# 8x8.net
KiCad netlist of a schematic drawn in EAGLE
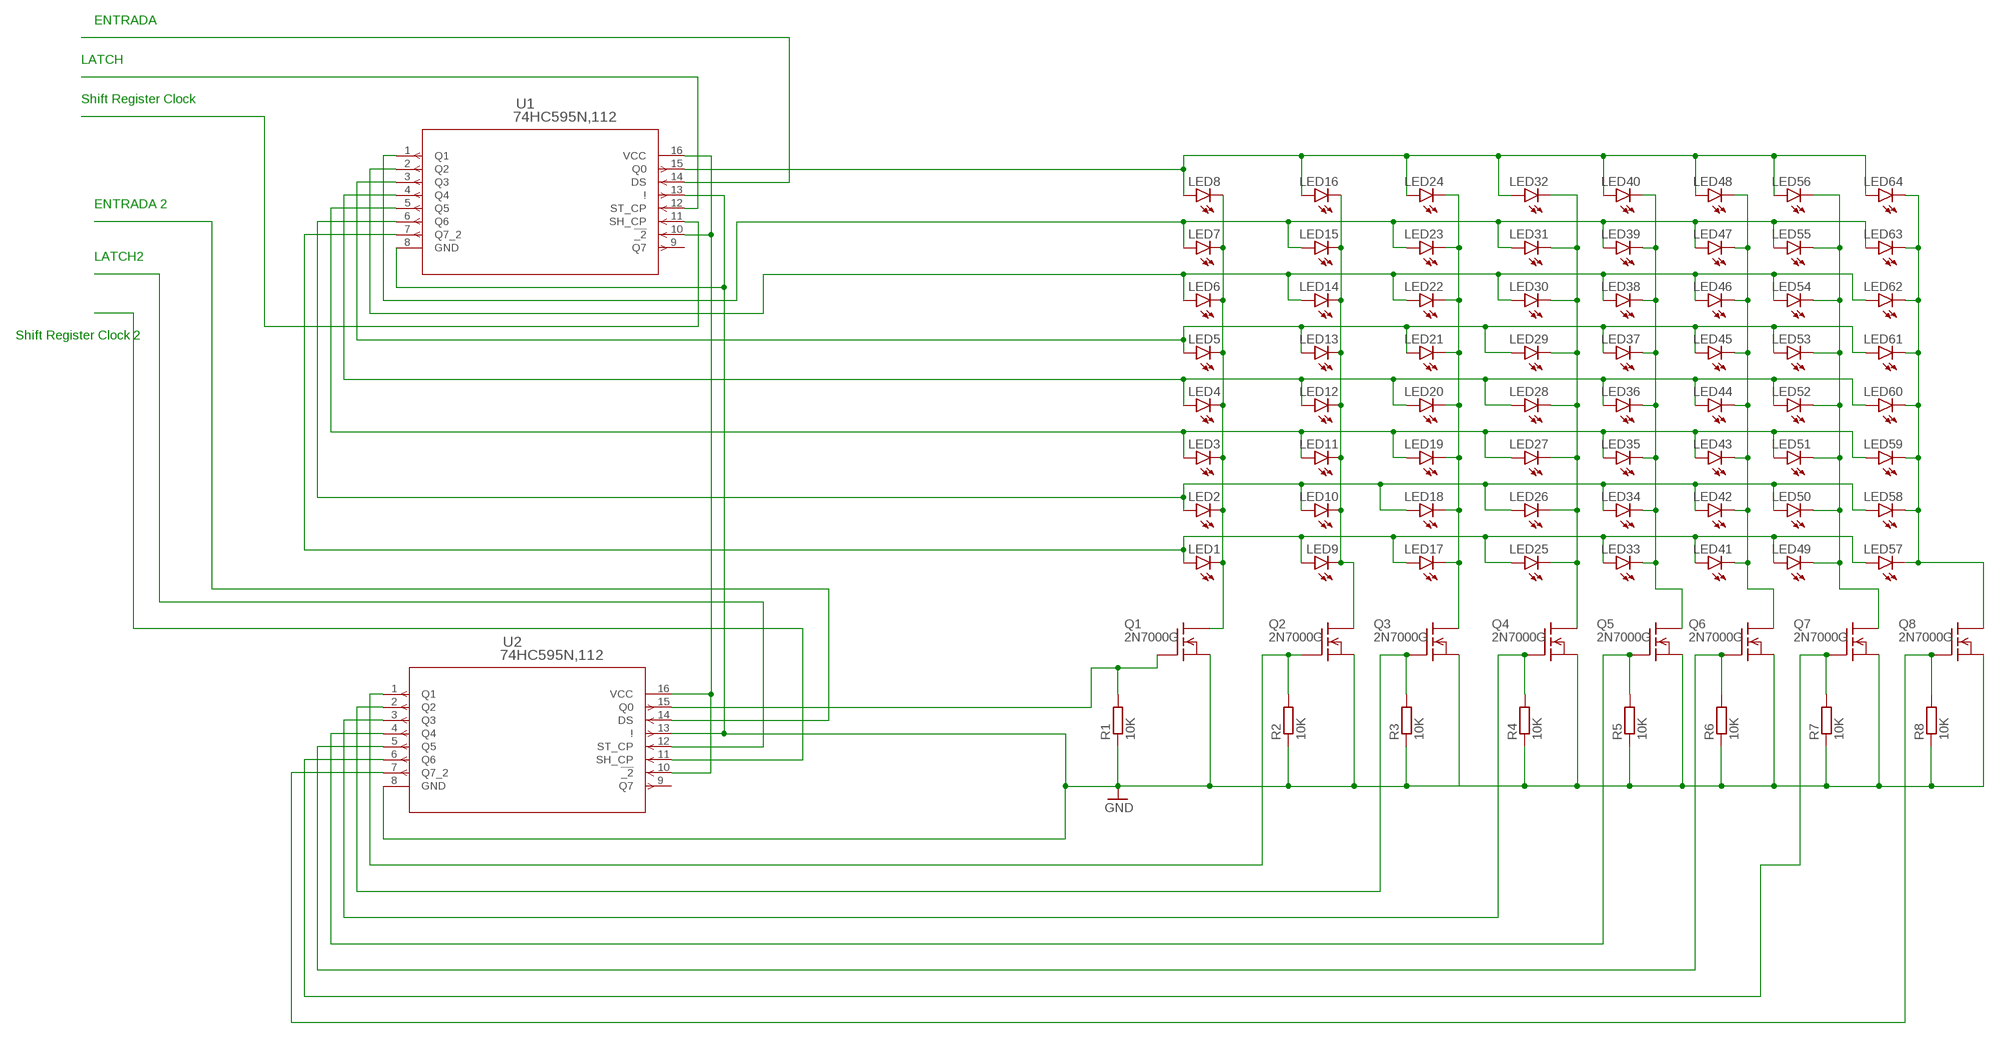
[diagram p0: schematic, sheet 1]

(export (version "E")
  (design (tool "Eeschema 10.0.6"))
  (components
    (comp (ref "LED1")
      (value "LED3MM")
      (footprint "eagle-import:LED3MM")
      (libsource (lib "eagle-import") (part "LED3MM"))
    )
    (comp (ref "LED2")
      (value "LED3MM")
      (footprint "eagle-import:LED3MM")
      (libsource (lib "eagle-import") (part "LED3MM"))
    )
    (comp (ref "LED3")
      (value "LED3MM")
      (footprint "eagle-import:LED3MM")
      (libsource (lib "eagle-import") (part "LED3MM"))
    )
    (comp (ref "LED4")
      (value "LED3MM")
      (footprint "eagle-import:LED3MM")
      (libsource (lib "eagle-import") (part "LED3MM"))
    )
    (comp (ref "LED5")
      (value "LED3MM")
      (footprint "eagle-import:LED3MM")
      (libsource (lib "eagle-import") (part "LED3MM"))
    )
    (comp (ref "LED6")
      (value "LED3MM")
      (footprint "eagle-import:LED3MM")
      (libsource (lib "eagle-import") (part "LED3MM"))
    )
    (comp (ref "LED7")
      (value "LED3MM")
      (footprint "eagle-import:LED3MM")
      (libsource (lib "eagle-import") (part "LED3MM"))
    )
    (comp (ref "LED8")
      (value "LED3MM")
      (footprint "eagle-import:LED3MM")
      (libsource (lib "eagle-import") (part "LED3MM"))
    )
    (comp (ref "LED9")
      (value "LED3MM")
      (footprint "eagle-import:LED3MM")
      (libsource (lib "eagle-import") (part "LED3MM"))
    )
    (comp (ref "LED10")
      (value "LED3MM")
      (footprint "eagle-import:LED3MM")
      (libsource (lib "eagle-import") (part "LED3MM"))
    )
    (comp (ref "LED11")
      (value "LED3MM")
      (footprint "eagle-import:LED3MM")
      (libsource (lib "eagle-import") (part "LED3MM"))
    )
    (comp (ref "LED12")
      (value "LED3MM")
      (footprint "eagle-import:LED3MM")
      (libsource (lib "eagle-import") (part "LED3MM"))
    )
    (comp (ref "LED13")
      (value "LED3MM")
      (footprint "eagle-import:LED3MM")
      (libsource (lib "eagle-import") (part "LED3MM"))
    )
    (comp (ref "LED14")
      (value "LED3MM")
      (footprint "eagle-import:LED3MM")
      (libsource (lib "eagle-import") (part "LED3MM"))
    )
    (comp (ref "LED15")
      (value "LED3MM")
      (footprint "eagle-import:LED3MM")
      (libsource (lib "eagle-import") (part "LED3MM"))
    )
    (comp (ref "LED16")
      (value "LED3MM")
      (footprint "eagle-import:LED3MM")
      (libsource (lib "eagle-import") (part "LED3MM"))
    )
    (comp (ref "LED17")
      (value "LED3MM")
      (footprint "eagle-import:LED3MM")
      (libsource (lib "eagle-import") (part "LED3MM"))
    )
    (comp (ref "LED18")
      (value "LED3MM")
      (footprint "eagle-import:LED3MM")
      (libsource (lib "eagle-import") (part "LED3MM"))
    )
    (comp (ref "LED19")
      (value "LED3MM")
      (footprint "eagle-import:LED3MM")
      (libsource (lib "eagle-import") (part "LED3MM"))
    )
    (comp (ref "LED20")
      (value "LED3MM")
      (footprint "eagle-import:LED3MM")
      (libsource (lib "eagle-import") (part "LED3MM"))
    )
    (comp (ref "LED21")
      (value "LED3MM")
      (footprint "eagle-import:LED3MM")
      (libsource (lib "eagle-import") (part "LED3MM"))
    )
    (comp (ref "LED22")
      (value "LED3MM")
      (footprint "eagle-import:LED3MM")
      (libsource (lib "eagle-import") (part "LED3MM"))
    )
    (comp (ref "LED23")
      (value "LED3MM")
      (footprint "eagle-import:LED3MM")
      (libsource (lib "eagle-import") (part "LED3MM"))
    )
    (comp (ref "LED24")
      (value "LED3MM")
      (footprint "eagle-import:LED3MM")
      (libsource (lib "eagle-import") (part "LED3MM"))
    )
    (comp (ref "LED25")
      (value "LED3MM")
      (footprint "eagle-import:LED3MM")
      (libsource (lib "eagle-import") (part "LED3MM"))
    )
    (comp (ref "LED26")
      (value "LED3MM")
      (footprint "eagle-import:LED3MM")
      (libsource (lib "eagle-import") (part "LED3MM"))
    )
    (comp (ref "LED27")
      (value "LED3MM")
      (footprint "eagle-import:LED3MM")
      (libsource (lib "eagle-import") (part "LED3MM"))
    )
    (comp (ref "LED28")
      (value "LED3MM")
      (footprint "eagle-import:LED3MM")
      (libsource (lib "eagle-import") (part "LED3MM"))
    )
    (comp (ref "LED29")
      (value "LED3MM")
      (footprint "eagle-import:LED3MM")
      (libsource (lib "eagle-import") (part "LED3MM"))
    )
    (comp (ref "LED30")
      (value "LED3MM")
      (footprint "eagle-import:LED3MM")
      (libsource (lib "eagle-import") (part "LED3MM"))
    )
    (comp (ref "LED31")
      (value "LED3MM")
      (footprint "eagle-import:LED3MM")
      (libsource (lib "eagle-import") (part "LED3MM"))
    )
    (comp (ref "LED32")
      (value "LED3MM")
      (footprint "eagle-import:LED3MM")
      (libsource (lib "eagle-import") (part "LED3MM"))
    )
    (comp (ref "LED33")
      (value "LED3MM")
      (footprint "eagle-import:LED3MM")
      (libsource (lib "eagle-import") (part "LED3MM"))
    )
    (comp (ref "LED34")
      (value "LED3MM")
      (footprint "eagle-import:LED3MM")
      (libsource (lib "eagle-import") (part "LED3MM"))
    )
    (comp (ref "LED35")
      (value "LED3MM")
      (footprint "eagle-import:LED3MM")
      (libsource (lib "eagle-import") (part "LED3MM"))
    )
    (comp (ref "LED36")
      (value "LED3MM")
      (footprint "eagle-import:LED3MM")
      (libsource (lib "eagle-import") (part "LED3MM"))
    )
    (comp (ref "LED37")
      (value "LED3MM")
      (footprint "eagle-import:LED3MM")
      (libsource (lib "eagle-import") (part "LED3MM"))
    )
    (comp (ref "LED38")
      (value "LED3MM")
      (footprint "eagle-import:LED3MM")
      (libsource (lib "eagle-import") (part "LED3MM"))
    )
    (comp (ref "LED39")
      (value "LED3MM")
      (footprint "eagle-import:LED3MM")
      (libsource (lib "eagle-import") (part "LED3MM"))
    )
    (comp (ref "LED40")
      (value "LED3MM")
      (footprint "eagle-import:LED3MM")
      (libsource (lib "eagle-import") (part "LED3MM"))
    )
    (comp (ref "LED41")
      (value "LED3MM")
      (footprint "eagle-import:LED3MM")
      (libsource (lib "eagle-import") (part "LED3MM"))
    )
    (comp (ref "LED42")
      (value "LED3MM")
      (footprint "eagle-import:LED3MM")
      (libsource (lib "eagle-import") (part "LED3MM"))
    )
    (comp (ref "LED43")
      (value "LED3MM")
      (footprint "eagle-import:LED3MM")
      (libsource (lib "eagle-import") (part "LED3MM"))
    )
    (comp (ref "LED44")
      (value "LED3MM")
      (footprint "eagle-import:LED3MM")
      (libsource (lib "eagle-import") (part "LED3MM"))
    )
    (comp (ref "LED45")
      (value "LED3MM")
      (footprint "eagle-import:LED3MM")
      (libsource (lib "eagle-import") (part "LED3MM"))
    )
    (comp (ref "LED46")
      (value "LED3MM")
      (footprint "eagle-import:LED3MM")
      (libsource (lib "eagle-import") (part "LED3MM"))
    )
    (comp (ref "LED47")
      (value "LED3MM")
      (footprint "eagle-import:LED3MM")
      (libsource (lib "eagle-import") (part "LED3MM"))
    )
    (comp (ref "LED48")
      (value "LED3MM")
      (footprint "eagle-import:LED3MM")
      (libsource (lib "eagle-import") (part "LED3MM"))
    )
    (comp (ref "LED49")
      (value "LED3MM")
      (footprint "eagle-import:LED3MM")
      (libsource (lib "eagle-import") (part "LED3MM"))
    )
    (comp (ref "LED50")
      (value "LED3MM")
      (footprint "eagle-import:LED3MM")
      (libsource (lib "eagle-import") (part "LED3MM"))
    )
    (comp (ref "LED51")
      (value "LED3MM")
      (footprint "eagle-import:LED3MM")
      (libsource (lib "eagle-import") (part "LED3MM"))
    )
    (comp (ref "LED52")
      (value "LED3MM")
      (footprint "eagle-import:LED3MM")
      (libsource (lib "eagle-import") (part "LED3MM"))
    )
    (comp (ref "LED53")
      (value "LED3MM")
      (footprint "eagle-import:LED3MM")
      (libsource (lib "eagle-import") (part "LED3MM"))
    )
    (comp (ref "LED54")
      (value "LED3MM")
      (footprint "eagle-import:LED3MM")
      (libsource (lib "eagle-import") (part "LED3MM"))
    )
    (comp (ref "LED55")
      (value "LED3MM")
      (footprint "eagle-import:LED3MM")
      (libsource (lib "eagle-import") (part "LED3MM"))
    )
    (comp (ref "LED56")
      (value "LED3MM")
      (footprint "eagle-import:LED3MM")
      (libsource (lib "eagle-import") (part "LED3MM"))
    )
    (comp (ref "LED57")
      (value "LED3MM")
      (footprint "eagle-import:LED3MM")
      (libsource (lib "eagle-import") (part "LED3MM"))
    )
    (comp (ref "LED58")
      (value "LED3MM")
      (footprint "eagle-import:LED3MM")
      (libsource (lib "eagle-import") (part "LED3MM"))
    )
    (comp (ref "LED59")
      (value "LED3MM")
      (footprint "eagle-import:LED3MM")
      (libsource (lib "eagle-import") (part "LED3MM"))
    )
    (comp (ref "LED60")
      (value "LED3MM")
      (footprint "eagle-import:LED3MM")
      (libsource (lib "eagle-import") (part "LED3MM"))
    )
    (comp (ref "LED61")
      (value "LED3MM")
      (footprint "eagle-import:LED3MM")
      (libsource (lib "eagle-import") (part "LED3MM"))
    )
    (comp (ref "LED62")
      (value "LED3MM")
      (footprint "eagle-import:LED3MM")
      (libsource (lib "eagle-import") (part "LED3MM"))
    )
    (comp (ref "LED63")
      (value "LED3MM")
      (footprint "eagle-import:LED3MM")
      (libsource (lib "eagle-import") (part "LED3MM"))
    )
    (comp (ref "LED64")
      (value "LED3MM")
      (footprint "eagle-import:LED3MM")
      (libsource (lib "eagle-import") (part "LED3MM"))
    )
    (comp (ref "Q1")
      (value "2N7000G")
      (footprint "eagle-import:TO92-INLINE")
      (fields (field (name "MF") "ON Semiconductor"))
      (libsource (lib "eagle-import") (part "2N7000G"))
    )
    (comp (ref "Q2")
      (value "2N7000G")
      (footprint "eagle-import:TO92-INLINE")
      (fields (field (name "MF") "ON Semiconductor"))
      (libsource (lib "eagle-import") (part "2N7000G"))
    )
    (comp (ref "Q3")
      (value "2N7000G")
      (footprint "eagle-import:TO92-INLINE")
      (fields (field (name "MF") "ON Semiconductor"))
      (libsource (lib "eagle-import") (part "2N7000G"))
    )
    (comp (ref "Q4")
      (value "2N7000G")
      (footprint "eagle-import:TO92-INLINE")
      (fields (field (name "MF") "ON Semiconductor"))
      (libsource (lib "eagle-import") (part "2N7000G"))
    )
    (comp (ref "Q5")
      (value "2N7000G")
      (footprint "eagle-import:TO92-INLINE")
      (fields (field (name "MF") "ON Semiconductor"))
      (libsource (lib "eagle-import") (part "2N7000G"))
    )
    (comp (ref "Q6")
      (value "2N7000G")
      (footprint "eagle-import:TO92-INLINE")
      (fields (field (name "MF") "ON Semiconductor"))
      (libsource (lib "eagle-import") (part "2N7000G"))
    )
    (comp (ref "Q7")
      (value "2N7000G")
      (footprint "eagle-import:TO92-INLINE")
      (fields (field (name "MF") "ON Semiconductor"))
      (libsource (lib "eagle-import") (part "2N7000G"))
    )
    (comp (ref "Q8")
      (value "2N7000G")
      (footprint "eagle-import:TO92-INLINE")
      (fields (field (name "MF") "ON Semiconductor"))
      (libsource (lib "eagle-import") (part "2N7000G"))
    )
    (comp (ref "R1")
      (value "10K")
      (footprint "eagle-import:0204V")
      (fields (field (name "POPULARITY") "10000"))
      (libsource (lib "eagle-import") (part "R-EU_0204/2V"))
    )
    (comp (ref "R2")
      (value "10K")
      (footprint "eagle-import:0204V")
      (fields (field (name "POPULARITY") "10000"))
      (libsource (lib "eagle-import") (part "R-EU_0204/2V"))
    )
    (comp (ref "R3")
      (value "10K")
      (footprint "eagle-import:0204V")
      (fields (field (name "POPULARITY") "10000"))
      (libsource (lib "eagle-import") (part "R-EU_0204/2V"))
    )
    (comp (ref "R4")
      (value "10K")
      (footprint "eagle-import:0204V")
      (fields (field (name "POPULARITY") "10000"))
      (libsource (lib "eagle-import") (part "R-EU_0204/2V"))
    )
    (comp (ref "R5")
      (value "10K")
      (footprint "eagle-import:0204V")
      (fields (field (name "POPULARITY") "10000"))
      (libsource (lib "eagle-import") (part "R-EU_0204/2V"))
    )
    (comp (ref "R6")
      (value "10K")
      (footprint "eagle-import:0204V")
      (fields (field (name "POPULARITY") "10000"))
      (libsource (lib "eagle-import") (part "R-EU_0204/2V"))
    )
    (comp (ref "R7")
      (value "10K")
      (footprint "eagle-import:0204V")
      (fields (field (name "POPULARITY") "10000"))
      (libsource (lib "eagle-import") (part "R-EU_0204/2V"))
    )
    (comp (ref "R8")
      (value "10K")
      (footprint "eagle-import:0204V")
      (fields (field (name "POPULARITY") "10000"))
      (libsource (lib "eagle-import") (part "R-EU_0204/2V"))
    )
    (comp (ref "U1")
      (value "74HC595N,112")
      (footprint "eagle-import:SOT38-4_NXP")
      (libsource (lib "eagle-import") (part "74HC595N,112"))
    )
    (comp (ref "U2")
      (value "74HC595N,112")
      (footprint "eagle-import:SOT38-4_NXP")
      (libsource (lib "eagle-import") (part "74HC595N,112"))
    )
  )
  (nets
    (net (code "1") (name "GND") (class "Default")
      (node (ref "Q1") (pin "1") (pinfunction "SRC_1") (pintype "passive"))
      (node (ref "Q2") (pin "1") (pinfunction "SRC_1") (pintype "passive"))
      (node (ref "Q3") (pin "1") (pinfunction "SRC_1") (pintype "passive"))
      (node (ref "Q4") (pin "1") (pinfunction "SRC_1") (pintype "passive"))
      (node (ref "Q5") (pin "1") (pinfunction "SRC_1") (pintype "passive"))
      (node (ref "Q6") (pin "1") (pinfunction "SRC_1") (pintype "passive"))
      (node (ref "Q7") (pin "1") (pinfunction "SRC_1") (pintype "passive"))
      (node (ref "Q8") (pin "1") (pinfunction "SRC_1") (pintype "passive"))
      (node (ref "R1") (pin "1") (pinfunction "1_1") (pintype "passive"))
      (node (ref "R2") (pin "1") (pinfunction "1_1") (pintype "passive"))
      (node (ref "R3") (pin "1") (pinfunction "1_1") (pintype "passive"))
      (node (ref "R4") (pin "1") (pinfunction "1_1") (pintype "passive"))
      (node (ref "R5") (pin "1") (pinfunction "1_1") (pintype "passive"))
      (node (ref "R6") (pin "1") (pinfunction "1_1") (pintype "passive"))
      (node (ref "R7") (pin "1") (pinfunction "1_1") (pintype "passive"))
      (node (ref "R8") (pin "1") (pinfunction "1_1") (pintype "passive"))
      (node (ref "U1") (pin "13") (pinfunction "~_13") (pintype "output"))
      (node (ref "U1") (pin "8") (pinfunction "GND_8") (pintype "power_in"))
      (node (ref "U2") (pin "13") (pinfunction "~_13") (pintype "output"))
      (node (ref "U2") (pin "8") (pinfunction "GND_8") (pintype "power_in"))
    )
    (net (code "2") (name "Net-(LED1-C)") (class "Default")
      (node (ref "LED1") (pin "K") (pinfunction "C_K") (pintype "passive"))
      (node (ref "LED2") (pin "K") (pinfunction "C_K") (pintype "passive"))
      (node (ref "LED3") (pin "K") (pinfunction "C_K") (pintype "passive"))
      (node (ref "LED4") (pin "K") (pinfunction "C_K") (pintype "passive"))
      (node (ref "LED5") (pin "K") (pinfunction "C_K") (pintype "passive"))
      (node (ref "LED6") (pin "K") (pinfunction "C_K") (pintype "passive"))
      (node (ref "LED7") (pin "K") (pinfunction "C_K") (pintype "passive"))
      (node (ref "LED8") (pin "K") (pinfunction "C_K") (pintype "passive"))
      (node (ref "Q1") (pin "3") (pinfunction "DRN_3") (pintype "passive"))
    )
    (net (code "3") (name "Net-(LED10-C)") (class "Default")
      (node (ref "LED10") (pin "K") (pinfunction "C_K") (pintype "passive"))
      (node (ref "LED11") (pin "K") (pinfunction "C_K") (pintype "passive"))
      (node (ref "LED12") (pin "K") (pinfunction "C_K") (pintype "passive"))
      (node (ref "LED13") (pin "K") (pinfunction "C_K") (pintype "passive"))
      (node (ref "LED14") (pin "K") (pinfunction "C_K") (pintype "passive"))
      (node (ref "LED15") (pin "K") (pinfunction "C_K") (pintype "passive"))
      (node (ref "LED16") (pin "K") (pinfunction "C_K") (pintype "passive"))
      (node (ref "LED9") (pin "K") (pinfunction "C_K") (pintype "passive"))
      (node (ref "Q2") (pin "3") (pinfunction "DRN_3") (pintype "passive"))
    )
    (net (code "4") (name "Net-(LED17-C)") (class "Default")
      (node (ref "LED17") (pin "K") (pinfunction "C_K") (pintype "passive"))
      (node (ref "LED18") (pin "K") (pinfunction "C_K") (pintype "passive"))
      (node (ref "LED19") (pin "K") (pinfunction "C_K") (pintype "passive"))
      (node (ref "LED20") (pin "K") (pinfunction "C_K") (pintype "passive"))
      (node (ref "LED21") (pin "K") (pinfunction "C_K") (pintype "passive"))
      (node (ref "LED22") (pin "K") (pinfunction "C_K") (pintype "passive"))
      (node (ref "LED23") (pin "K") (pinfunction "C_K") (pintype "passive"))
      (node (ref "LED24") (pin "K") (pinfunction "C_K") (pintype "passive"))
      (node (ref "Q3") (pin "3") (pinfunction "DRN_3") (pintype "passive"))
    )
    (net (code "5") (name "Net-(LED25-C)") (class "Default")
      (node (ref "LED25") (pin "K") (pinfunction "C_K") (pintype "passive"))
      (node (ref "LED26") (pin "K") (pinfunction "C_K") (pintype "passive"))
      (node (ref "LED27") (pin "K") (pinfunction "C_K") (pintype "passive"))
      (node (ref "LED28") (pin "K") (pinfunction "C_K") (pintype "passive"))
      (node (ref "LED29") (pin "K") (pinfunction "C_K") (pintype "passive"))
      (node (ref "LED30") (pin "K") (pinfunction "C_K") (pintype "passive"))
      (node (ref "LED31") (pin "K") (pinfunction "C_K") (pintype "passive"))
      (node (ref "LED32") (pin "K") (pinfunction "C_K") (pintype "passive"))
      (node (ref "Q4") (pin "3") (pinfunction "DRN_3") (pintype "passive"))
    )
    (net (code "6") (name "Net-(LED33-C)") (class "Default")
      (node (ref "LED33") (pin "K") (pinfunction "C_K") (pintype "passive"))
      (node (ref "LED34") (pin "K") (pinfunction "C_K") (pintype "passive"))
      (node (ref "LED35") (pin "K") (pinfunction "C_K") (pintype "passive"))
      (node (ref "LED36") (pin "K") (pinfunction "C_K") (pintype "passive"))
      (node (ref "LED37") (pin "K") (pinfunction "C_K") (pintype "passive"))
      (node (ref "LED38") (pin "K") (pinfunction "C_K") (pintype "passive"))
      (node (ref "LED39") (pin "K") (pinfunction "C_K") (pintype "passive"))
      (node (ref "LED40") (pin "K") (pinfunction "C_K") (pintype "passive"))
      (node (ref "Q5") (pin "3") (pinfunction "DRN_3") (pintype "passive"))
    )
    (net (code "7") (name "Net-(LED41-C)") (class "Default")
      (node (ref "LED41") (pin "K") (pinfunction "C_K") (pintype "passive"))
      (node (ref "LED42") (pin "K") (pinfunction "C_K") (pintype "passive"))
      (node (ref "LED43") (pin "K") (pinfunction "C_K") (pintype "passive"))
      (node (ref "LED44") (pin "K") (pinfunction "C_K") (pintype "passive"))
      (node (ref "LED45") (pin "K") (pinfunction "C_K") (pintype "passive"))
      (node (ref "LED46") (pin "K") (pinfunction "C_K") (pintype "passive"))
      (node (ref "LED47") (pin "K") (pinfunction "C_K") (pintype "passive"))
      (node (ref "LED48") (pin "K") (pinfunction "C_K") (pintype "passive"))
      (node (ref "Q6") (pin "3") (pinfunction "DRN_3") (pintype "passive"))
    )
    (net (code "8") (name "Net-(LED49-C)") (class "Default")
      (node (ref "LED49") (pin "K") (pinfunction "C_K") (pintype "passive"))
      (node (ref "LED50") (pin "K") (pinfunction "C_K") (pintype "passive"))
      (node (ref "LED51") (pin "K") (pinfunction "C_K") (pintype "passive"))
      (node (ref "LED52") (pin "K") (pinfunction "C_K") (pintype "passive"))
      (node (ref "LED53") (pin "K") (pinfunction "C_K") (pintype "passive"))
      (node (ref "LED54") (pin "K") (pinfunction "C_K") (pintype "passive"))
      (node (ref "LED55") (pin "K") (pinfunction "C_K") (pintype "passive"))
      (node (ref "LED56") (pin "K") (pinfunction "C_K") (pintype "passive"))
      (node (ref "Q7") (pin "3") (pinfunction "DRN_3") (pintype "passive"))
    )
    (net (code "9") (name "Net-(LED57-C)") (class "Default")
      (node (ref "LED57") (pin "K") (pinfunction "C_K") (pintype "passive"))
      (node (ref "LED58") (pin "K") (pinfunction "C_K") (pintype "passive"))
      (node (ref "LED59") (pin "K") (pinfunction "C_K") (pintype "passive"))
      (node (ref "LED60") (pin "K") (pinfunction "C_K") (pintype "passive"))
      (node (ref "LED61") (pin "K") (pinfunction "C_K") (pintype "passive"))
      (node (ref "LED62") (pin "K") (pinfunction "C_K") (pintype "passive"))
      (node (ref "LED63") (pin "K") (pinfunction "C_K") (pintype "passive"))
      (node (ref "LED64") (pin "K") (pinfunction "C_K") (pintype "passive"))
      (node (ref "Q8") (pin "3") (pinfunction "DRN_3") (pintype "passive"))
    )
    (net (code "10") (name "Net-(Q1-GATE)") (class "Default")
      (node (ref "Q1") (pin "2") (pinfunction "GATE_2") (pintype "passive"))
      (node (ref "R1") (pin "2") (pinfunction "2_2") (pintype "passive"))
      (node (ref "U2") (pin "15") (pinfunction "Q0_15") (pintype "output"))
    )
    (net (code "11") (name "Net-(Q2-GATE)") (class "Default")
      (node (ref "Q2") (pin "2") (pinfunction "GATE_2") (pintype "passive"))
      (node (ref "R2") (pin "2") (pinfunction "2_2") (pintype "passive"))
      (node (ref "U2") (pin "1") (pinfunction "Q1_1") (pintype "output"))
    )
    (net (code "12") (name "Net-(Q3-GATE)") (class "Default")
      (node (ref "Q3") (pin "2") (pinfunction "GATE_2") (pintype "passive"))
      (node (ref "R3") (pin "2") (pinfunction "2_2") (pintype "passive"))
      (node (ref "U2") (pin "2") (pinfunction "Q2_2") (pintype "output"))
    )
    (net (code "13") (name "Net-(Q4-GATE)") (class "Default")
      (node (ref "Q4") (pin "2") (pinfunction "GATE_2") (pintype "passive"))
      (node (ref "R4") (pin "2") (pinfunction "2_2") (pintype "passive"))
      (node (ref "U2") (pin "3") (pinfunction "Q3_3") (pintype "output"))
    )
    (net (code "14") (name "Net-(Q5-GATE)") (class "Default")
      (node (ref "Q5") (pin "2") (pinfunction "GATE_2") (pintype "passive"))
      (node (ref "R5") (pin "2") (pinfunction "2_2") (pintype "passive"))
      (node (ref "U2") (pin "4") (pinfunction "Q4_4") (pintype "output"))
    )
    (net (code "15") (name "Net-(Q6-GATE)") (class "Default")
      (node (ref "Q6") (pin "2") (pinfunction "GATE_2") (pintype "passive"))
      (node (ref "R6") (pin "2") (pinfunction "2_2") (pintype "passive"))
      (node (ref "U2") (pin "5") (pinfunction "Q5_5") (pintype "output"))
    )
    (net (code "16") (name "Net-(Q7-GATE)") (class "Default")
      (node (ref "Q7") (pin "2") (pinfunction "GATE_2") (pintype "passive"))
      (node (ref "R7") (pin "2") (pinfunction "2_2") (pintype "passive"))
      (node (ref "U2") (pin "6") (pinfunction "Q6_6") (pintype "output"))
    )
    (net (code "17") (name "Net-(Q8-GATE)") (class "Default")
      (node (ref "Q8") (pin "2") (pinfunction "GATE_2") (pintype "passive"))
      (node (ref "R8") (pin "2") (pinfunction "2_2") (pintype "passive"))
      (node (ref "U2") (pin "7") (pinfunction "Q7_2_7") (pintype "output"))
    )
    (net (code "18") (name "Net-(U1-Q0)") (class "Default")
      (node (ref "LED16") (pin "A") (pinfunction "A_A") (pintype "passive"))
      (node (ref "LED24") (pin "A") (pinfunction "A_A") (pintype "passive"))
      (node (ref "LED32") (pin "A") (pinfunction "A_A") (pintype "passive"))
      (node (ref "LED40") (pin "A") (pinfunction "A_A") (pintype "passive"))
      (node (ref "LED48") (pin "A") (pinfunction "A_A") (pintype "passive"))
      (node (ref "LED56") (pin "A") (pinfunction "A_A") (pintype "passive"))
      (node (ref "LED64") (pin "A") (pinfunction "A_A") (pintype "passive"))
      (node (ref "LED8") (pin "A") (pinfunction "A_A") (pintype "passive"))
      (node (ref "U1") (pin "15") (pinfunction "Q0_15") (pintype "output"))
    )
    (net (code "19") (name "Net-(U1-Q1)") (class "Default")
      (node (ref "LED15") (pin "A") (pinfunction "A_A") (pintype "passive"))
      (node (ref "LED23") (pin "A") (pinfunction "A_A") (pintype "passive"))
      (node (ref "LED31") (pin "A") (pinfunction "A_A") (pintype "passive"))
      (node (ref "LED39") (pin "A") (pinfunction "A_A") (pintype "passive"))
      (node (ref "LED47") (pin "A") (pinfunction "A_A") (pintype "passive"))
      (node (ref "LED55") (pin "A") (pinfunction "A_A") (pintype "passive"))
      (node (ref "LED63") (pin "A") (pinfunction "A_A") (pintype "passive"))
      (node (ref "LED7") (pin "A") (pinfunction "A_A") (pintype "passive"))
      (node (ref "U1") (pin "1") (pinfunction "Q1_1") (pintype "output"))
    )
    (net (code "20") (name "Net-(U1-Q2)") (class "Default")
      (node (ref "LED14") (pin "A") (pinfunction "A_A") (pintype "passive"))
      (node (ref "LED22") (pin "A") (pinfunction "A_A") (pintype "passive"))
      (node (ref "LED30") (pin "A") (pinfunction "A_A") (pintype "passive"))
      (node (ref "LED38") (pin "A") (pinfunction "A_A") (pintype "passive"))
      (node (ref "LED46") (pin "A") (pinfunction "A_A") (pintype "passive"))
      (node (ref "LED54") (pin "A") (pinfunction "A_A") (pintype "passive"))
      (node (ref "LED6") (pin "A") (pinfunction "A_A") (pintype "passive"))
      (node (ref "LED62") (pin "A") (pinfunction "A_A") (pintype "passive"))
      (node (ref "U1") (pin "2") (pinfunction "Q2_2") (pintype "output"))
    )
    (net (code "21") (name "Net-(U1-Q3)") (class "Default")
      (node (ref "LED13") (pin "A") (pinfunction "A_A") (pintype "passive"))
      (node (ref "LED21") (pin "A") (pinfunction "A_A") (pintype "passive"))
      (node (ref "LED29") (pin "A") (pinfunction "A_A") (pintype "passive"))
      (node (ref "LED37") (pin "A") (pinfunction "A_A") (pintype "passive"))
      (node (ref "LED45") (pin "A") (pinfunction "A_A") (pintype "passive"))
      (node (ref "LED5") (pin "A") (pinfunction "A_A") (pintype "passive"))
      (node (ref "LED53") (pin "A") (pinfunction "A_A") (pintype "passive"))
      (node (ref "LED61") (pin "A") (pinfunction "A_A") (pintype "passive"))
      (node (ref "U1") (pin "3") (pinfunction "Q3_3") (pintype "output"))
    )
    (net (code "22") (name "Net-(U1-Q4)") (class "Default")
      (node (ref "LED12") (pin "A") (pinfunction "A_A") (pintype "passive"))
      (node (ref "LED20") (pin "A") (pinfunction "A_A") (pintype "passive"))
      (node (ref "LED28") (pin "A") (pinfunction "A_A") (pintype "passive"))
      (node (ref "LED36") (pin "A") (pinfunction "A_A") (pintype "passive"))
      (node (ref "LED4") (pin "A") (pinfunction "A_A") (pintype "passive"))
      (node (ref "LED44") (pin "A") (pinfunction "A_A") (pintype "passive"))
      (node (ref "LED52") (pin "A") (pinfunction "A_A") (pintype "passive"))
      (node (ref "LED60") (pin "A") (pinfunction "A_A") (pintype "passive"))
      (node (ref "U1") (pin "4") (pinfunction "Q4_4") (pintype "output"))
    )
    (net (code "23") (name "Net-(U1-Q5)") (class "Default")
      (node (ref "LED11") (pin "A") (pinfunction "A_A") (pintype "passive"))
      (node (ref "LED19") (pin "A") (pinfunction "A_A") (pintype "passive"))
      (node (ref "LED27") (pin "A") (pinfunction "A_A") (pintype "passive"))
      (node (ref "LED3") (pin "A") (pinfunction "A_A") (pintype "passive"))
      (node (ref "LED35") (pin "A") (pinfunction "A_A") (pintype "passive"))
      (node (ref "LED43") (pin "A") (pinfunction "A_A") (pintype "passive"))
      (node (ref "LED51") (pin "A") (pinfunction "A_A") (pintype "passive"))
      (node (ref "LED59") (pin "A") (pinfunction "A_A") (pintype "passive"))
      (node (ref "U1") (pin "5") (pinfunction "Q5_5") (pintype "output"))
    )
    (net (code "24") (name "Net-(U1-Q6)") (class "Default")
      (node (ref "LED10") (pin "A") (pinfunction "A_A") (pintype "passive"))
      (node (ref "LED18") (pin "A") (pinfunction "A_A") (pintype "passive"))
      (node (ref "LED2") (pin "A") (pinfunction "A_A") (pintype "passive"))
      (node (ref "LED26") (pin "A") (pinfunction "A_A") (pintype "passive"))
      (node (ref "LED34") (pin "A") (pinfunction "A_A") (pintype "passive"))
      (node (ref "LED42") (pin "A") (pinfunction "A_A") (pintype "passive"))
      (node (ref "LED50") (pin "A") (pinfunction "A_A") (pintype "passive"))
      (node (ref "LED58") (pin "A") (pinfunction "A_A") (pintype "passive"))
      (node (ref "U1") (pin "6") (pinfunction "Q6_6") (pintype "output"))
    )
    (net (code "25") (name "Net-(U1-Q7_2)") (class "Default")
      (node (ref "LED1") (pin "A") (pinfunction "A_A") (pintype "passive"))
      (node (ref "LED17") (pin "A") (pinfunction "A_A") (pintype "passive"))
      (node (ref "LED25") (pin "A") (pinfunction "A_A") (pintype "passive"))
      (node (ref "LED33") (pin "A") (pinfunction "A_A") (pintype "passive"))
      (node (ref "LED41") (pin "A") (pinfunction "A_A") (pintype "passive"))
      (node (ref "LED49") (pin "A") (pinfunction "A_A") (pintype "passive"))
      (node (ref "LED57") (pin "A") (pinfunction "A_A") (pintype "passive"))
      (node (ref "LED9") (pin "A") (pinfunction "A_A") (pintype "passive"))
      (node (ref "U1") (pin "7") (pinfunction "Q7_2_7") (pintype "output"))
    )
    (net (code "26") (name "Net-(U1-VCC)") (class "Default")
      (node (ref "U1") (pin "10") (pinfunction "~{_2}_10") (pintype "input"))
      (node (ref "U1") (pin "16") (pinfunction "VCC_16") (pintype "power_in"))
      (node (ref "U2") (pin "10") (pinfunction "~{_2}_10") (pintype "input"))
      (node (ref "U2") (pin "16") (pinfunction "VCC_16") (pintype "power_in"))
    )
    (net (code "27") (name "unconnected-(U1-DS-Pad14)") (class "Default")
      (node (ref "U1") (pin "14") (pinfunction "DS_14") (pintype "input"))
    )
    (net (code "28") (name "unconnected-(U1-Q7-Pad9)") (class "Default")
      (node (ref "U1") (pin "9") (pinfunction "Q7_9") (pintype "output"))
    )
    (net (code "29") (name "unconnected-(U1-SH_CP-Pad11)") (class "Default")
      (node (ref "U1") (pin "11") (pinfunction "SH_CP_11") (pintype "input"))
    )
    (net (code "30") (name "unconnected-(U1-ST_CP-Pad12)") (class "Default")
      (node (ref "U1") (pin "12") (pinfunction "ST_CP_12") (pintype "input"))
    )
    (net (code "31") (name "unconnected-(U2-DS-Pad14)") (class "Default")
      (node (ref "U2") (pin "14") (pinfunction "DS_14") (pintype "input"))
    )
    (net (code "32") (name "unconnected-(U2-Q7-Pad9)") (class "Default")
      (node (ref "U2") (pin "9") (pinfunction "Q7_9") (pintype "output"))
    )
    (net (code "33") (name "unconnected-(U2-SH_CP-Pad11)") (class "Default")
      (node (ref "U2") (pin "11") (pinfunction "SH_CP_11") (pintype "input"))
    )
    (net (code "34") (name "unconnected-(U2-ST_CP-Pad12)") (class "Default")
      (node (ref "U2") (pin "12") (pinfunction "ST_CP_12") (pintype "input"))
    )
  )
)
